# Dual_Horizontal_Breakout_Module.net
KiCad netlist of a schematic drawn in EAGLE
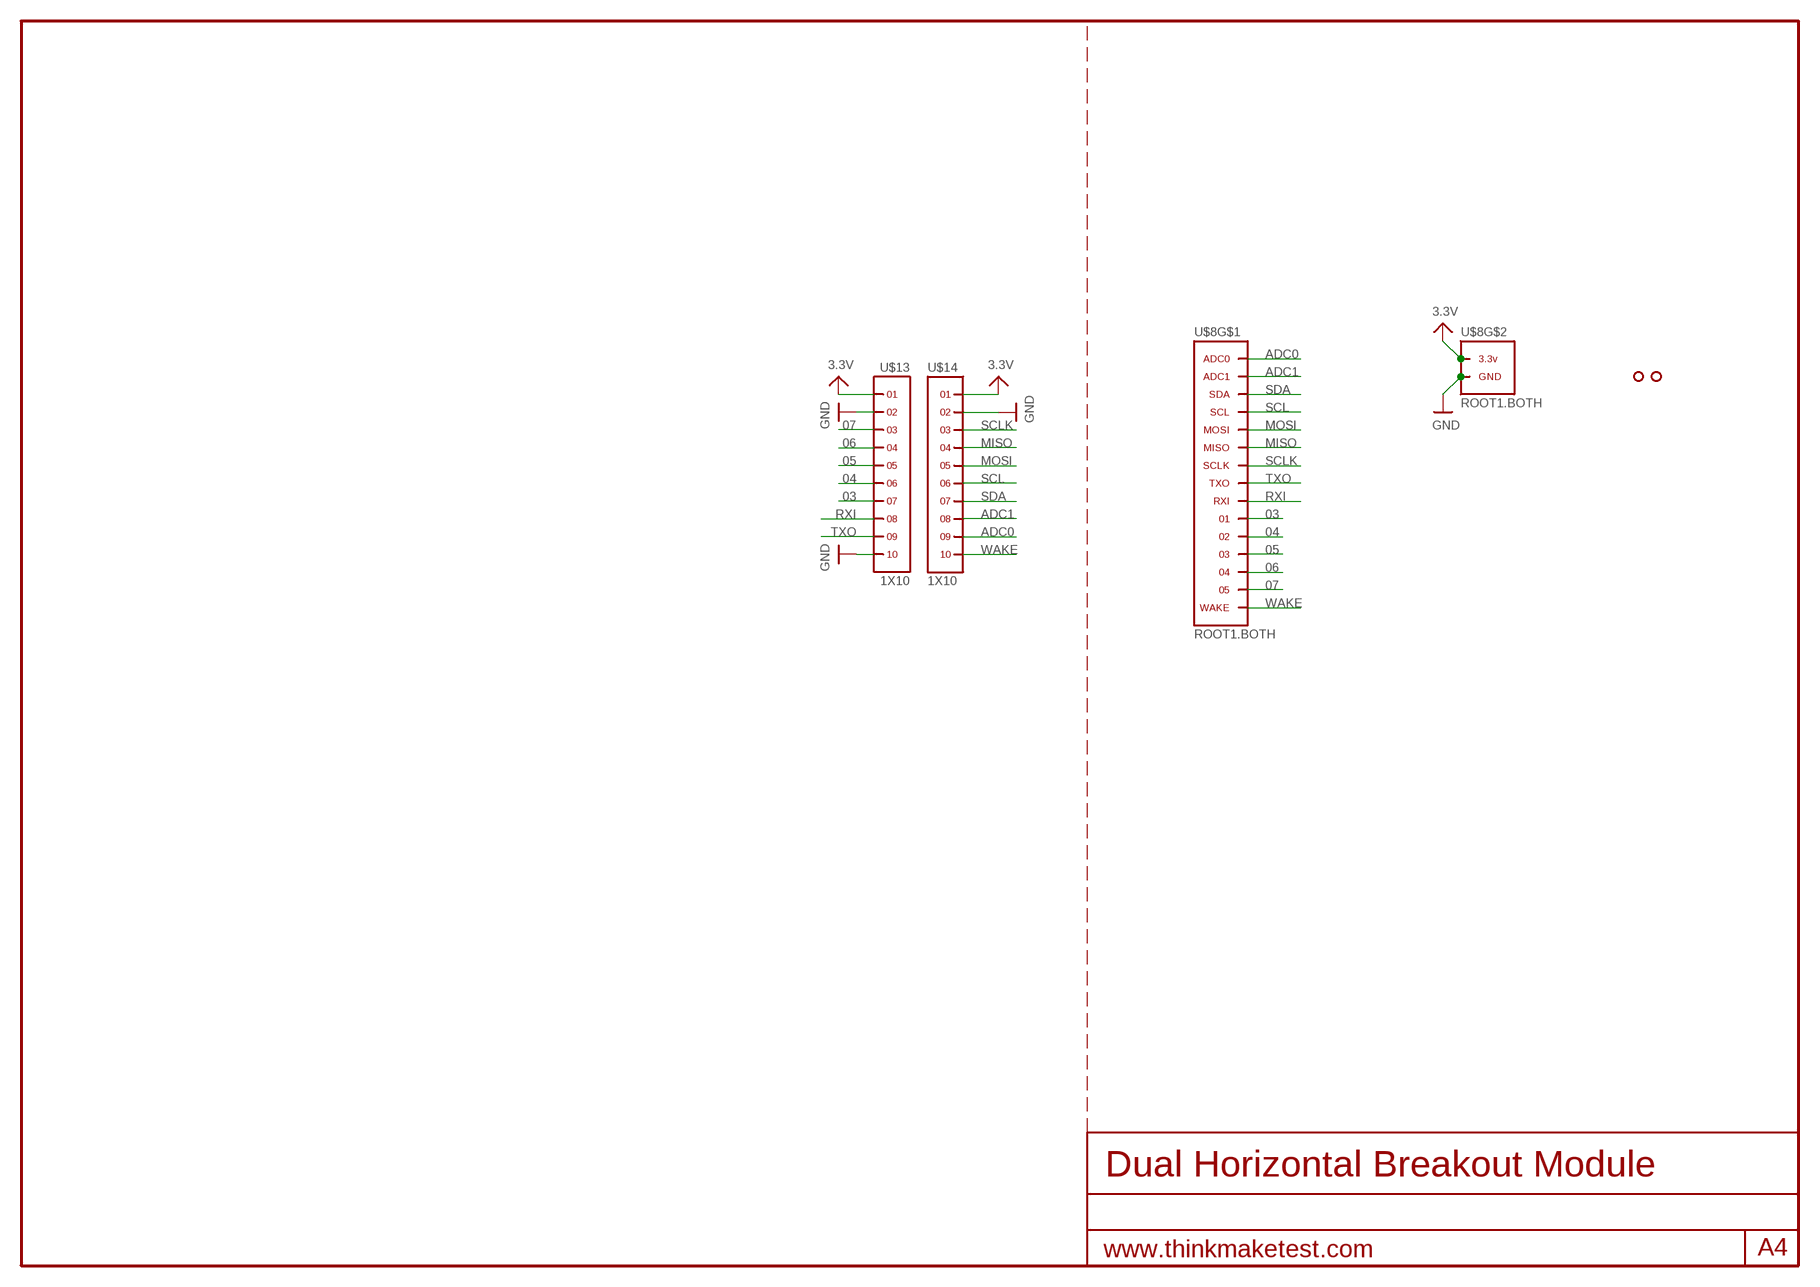
[diagram p0: schematic, sheet 1]

(export (version "E")
  (design (tool "Eeschema 10.0.6"))
  (components
    (comp (ref "U$3")
      (value "HOLE.2MM")
      (footprint "eagle-import:2MM")
      (libsource (lib "eagle-import") (part "HOLE.2MM"))
    )
    (comp (ref "U$4")
      (value "HOLE.2MM")
      (footprint "eagle-import:2MM")
      (libsource (lib "eagle-import") (part "HOLE.2MM"))
    )
    (comp (ref "U$8")
      (value "ROOT1.BOTH")
      (footprint "eagle-import:ROOT1.BOTH")
      (libsource (lib "eagle-import") (part "ROOT1.BOTH"))
    )
    (comp (ref "U$13")
      (value "1X10")
      (footprint "eagle-import:1X10")
      (libsource (lib "eagle-import") (part "1X10"))
    )
    (comp (ref "U$14")
      (value "1X10")
      (footprint "eagle-import:1X10")
      (libsource (lib "eagle-import") (part "1X10"))
    )
  )
  (nets
    (net (code "1") (name "/03") (class "Default")
      (node (ref "U$13") (pin "7") (pinfunction "7_7") (pintype "bidirectional"))
      (node (ref "U$8") (pin "03") (pinfunction "01_03") (pintype "bidirectional"))
      (node (ref "U$8") (pin "03@1") (pinfunction "01_03@1") (pintype "bidirectional"))
      (node (ref "U$8") (pin "03@VIA") (pinfunction "01_03@VIA") (pintype "bidirectional"))
    )
    (net (code "2") (name "/04") (class "Default")
      (node (ref "U$13") (pin "6") (pinfunction "6_6") (pintype "bidirectional"))
      (node (ref "U$8") (pin "04") (pinfunction "02_04") (pintype "bidirectional"))
      (node (ref "U$8") (pin "04@1") (pinfunction "02_04@1") (pintype "bidirectional"))
      (node (ref "U$8") (pin "04@VIA") (pinfunction "02_04@VIA") (pintype "bidirectional"))
    )
    (net (code "3") (name "/05") (class "Default")
      (node (ref "U$13") (pin "5") (pinfunction "5_5") (pintype "bidirectional"))
      (node (ref "U$8") (pin "05") (pinfunction "03_05") (pintype "bidirectional"))
      (node (ref "U$8") (pin "05@1") (pinfunction "03_05@1") (pintype "bidirectional"))
      (node (ref "U$8") (pin "05@VIA") (pinfunction "03_05@VIA") (pintype "bidirectional"))
    )
    (net (code "4") (name "/06") (class "Default")
      (node (ref "U$13") (pin "4") (pinfunction "4_4") (pintype "bidirectional"))
      (node (ref "U$8") (pin "06") (pinfunction "04_06") (pintype "bidirectional"))
      (node (ref "U$8") (pin "06@1") (pinfunction "04_06@1") (pintype "bidirectional"))
      (node (ref "U$8") (pin "06@VIA") (pinfunction "04_06@VIA") (pintype "bidirectional"))
    )
    (net (code "5") (name "/07") (class "Default")
      (node (ref "U$13") (pin "3") (pinfunction "3_3") (pintype "bidirectional"))
      (node (ref "U$8") (pin "07") (pinfunction "05_07") (pintype "bidirectional"))
      (node (ref "U$8") (pin "07@1") (pinfunction "05_07@1") (pintype "bidirectional"))
      (node (ref "U$8") (pin "07@VIA") (pinfunction "05_07@VIA") (pintype "bidirectional"))
    )
    (net (code "6") (name "/ADC0") (class "Default")
      (node (ref "U$14") (pin "9") (pinfunction "9_9") (pintype "bidirectional"))
      (node (ref "U$8") (pin "ADC0") (pinfunction "ADC0_ADC0") (pintype "bidirectional"))
      (node (ref "U$8") (pin "ADC0@1") (pinfunction "ADC0_ADC0@1") (pintype "bidirectional"))
      (node (ref "U$8") (pin "ADC0@VIA") (pinfunction "ADC0_ADC0@VIA") (pintype "bidirectional"))
    )
    (net (code "7") (name "/ADC1") (class "Default")
      (node (ref "U$14") (pin "8") (pinfunction "8_8") (pintype "bidirectional"))
      (node (ref "U$8") (pin "ADC1") (pinfunction "ADC1_ADC1") (pintype "bidirectional"))
      (node (ref "U$8") (pin "ADC1@1") (pinfunction "ADC1_ADC1@1") (pintype "bidirectional"))
      (node (ref "U$8") (pin "ADC1@VIA") (pinfunction "ADC1_ADC1@VIA") (pintype "bidirectional"))
    )
    (net (code "8") (name "/MISO") (class "Default")
      (node (ref "U$14") (pin "4") (pinfunction "4_4") (pintype "bidirectional"))
      (node (ref "U$8") (pin "MISO") (pinfunction "MISO_MISO") (pintype "bidirectional"))
      (node (ref "U$8") (pin "MISO@1") (pinfunction "MISO_MISO@1") (pintype "bidirectional"))
      (node (ref "U$8") (pin "MISO@VIA") (pinfunction "MISO_MISO@VIA") (pintype "bidirectional"))
    )
    (net (code "9") (name "/MOSI") (class "Default")
      (node (ref "U$14") (pin "5") (pinfunction "5_5") (pintype "bidirectional"))
      (node (ref "U$8") (pin "MOSI") (pinfunction "MOSI_MOSI") (pintype "bidirectional"))
      (node (ref "U$8") (pin "MOSI@1") (pinfunction "MOSI_MOSI@1") (pintype "bidirectional"))
      (node (ref "U$8") (pin "MOSI@VIA") (pinfunction "MOSI_MOSI@VIA") (pintype "bidirectional"))
    )
    (net (code "10") (name "/RXI") (class "Default")
      (node (ref "U$13") (pin "8") (pinfunction "8_8") (pintype "bidirectional"))
      (node (ref "U$8") (pin "02") (pinfunction "RXI_02") (pintype "bidirectional"))
      (node (ref "U$8") (pin "02@1") (pinfunction "RXI_02@1") (pintype "bidirectional"))
      (node (ref "U$8") (pin "02@VIA") (pinfunction "RXI_02@VIA") (pintype "bidirectional"))
    )
    (net (code "11") (name "/SCL") (class "Default")
      (node (ref "U$14") (pin "6") (pinfunction "6_6") (pintype "bidirectional"))
      (node (ref "U$8") (pin "SCL") (pinfunction "SCL_SCL") (pintype "bidirectional"))
      (node (ref "U$8") (pin "SCL@1") (pinfunction "SCL_SCL@1") (pintype "bidirectional"))
      (node (ref "U$8") (pin "SCL@VIA") (pinfunction "SCL_SCL@VIA") (pintype "bidirectional"))
    )
    (net (code "12") (name "/SCLK") (class "Default")
      (node (ref "U$14") (pin "3") (pinfunction "3_3") (pintype "bidirectional"))
      (node (ref "U$8") (pin "SCLK") (pinfunction "SCLK_SCLK") (pintype "bidirectional"))
      (node (ref "U$8") (pin "SCLK@1") (pinfunction "SCLK_SCLK@1") (pintype "bidirectional"))
      (node (ref "U$8") (pin "SCLK@VIA") (pinfunction "SCLK_SCLK@VIA") (pintype "bidirectional"))
    )
    (net (code "13") (name "/SDA") (class "Default")
      (node (ref "U$14") (pin "7") (pinfunction "7_7") (pintype "bidirectional"))
      (node (ref "U$8") (pin "SDA") (pinfunction "SDA_SDA") (pintype "bidirectional"))
      (node (ref "U$8") (pin "SDA@1") (pinfunction "SDA_SDA@1") (pintype "bidirectional"))
      (node (ref "U$8") (pin "SDA@VIA") (pinfunction "SDA_SDA@VIA") (pintype "bidirectional"))
    )
    (net (code "14") (name "/TXO") (class "Default")
      (node (ref "U$13") (pin "9") (pinfunction "9_9") (pintype "bidirectional"))
      (node (ref "U$8") (pin "01") (pinfunction "TXO_01") (pintype "bidirectional"))
      (node (ref "U$8") (pin "01@1") (pinfunction "TXO_01@1") (pintype "bidirectional"))
      (node (ref "U$8") (pin "01@VIA") (pinfunction "TXO_01@VIA") (pintype "bidirectional"))
    )
    (net (code "15") (name "/WAKE") (class "Default")
      (node (ref "U$14") (pin "10") (pinfunction "10_10") (pintype "bidirectional"))
      (node (ref "U$8") (pin "WAKE") (pinfunction "WAKE_WAKE") (pintype "bidirectional"))
      (node (ref "U$8") (pin "WAKE@1") (pinfunction "WAKE_WAKE@1") (pintype "bidirectional"))
      (node (ref "U$8") (pin "WAKE@VIA") (pinfunction "WAKE_WAKE@VIA") (pintype "bidirectional"))
    )
    (net (code "16") (name "3.3V") (class "Default")
      (node (ref "U$13") (pin "1") (pinfunction "1_1") (pintype "bidirectional"))
      (node (ref "U$14") (pin "1") (pinfunction "1_1") (pintype "bidirectional"))
      (node (ref "U$8") (pin "3.3V@1") (pinfunction "3.3V_3.3V@1") (pintype "bidirectional"))
      (node (ref "U$8") (pin "3.3V@10") (pinfunction "3.3V_3.3V@10") (pintype "bidirectional"))
      (node (ref "U$8") (pin "3.3V@2") (pinfunction "3.3V_3.3V@2") (pintype "bidirectional"))
      (node (ref "U$8") (pin "3.3V@3") (pinfunction "3.3V_3.3V@3") (pintype "bidirectional"))
      (node (ref "U$8") (pin "3.3V@4") (pinfunction "3.3V_3.3V@4") (pintype "bidirectional"))
      (node (ref "U$8") (pin "3.3V@5") (pinfunction "3.3V_3.3V@5") (pintype "bidirectional"))
      (node (ref "U$8") (pin "3.3V@6") (pinfunction "3.3V_3.3V@6") (pintype "bidirectional"))
      (node (ref "U$8") (pin "3.3V@7") (pinfunction "3.3V_3.3V@7") (pintype "bidirectional"))
      (node (ref "U$8") (pin "3.3V@8") (pinfunction "3.3V_3.3V@8") (pintype "bidirectional"))
      (node (ref "U$8") (pin "3.3V@9") (pinfunction "3.3V_3.3V@9") (pintype "bidirectional"))
      (node (ref "U$8") (pin "3.3V@VIA") (pinfunction "3.3V_3.3V@VIA") (pintype "bidirectional"))
    )
    (net (code "17") (name "GND") (class "Default")
      (node (ref "U$13") (pin "10") (pinfunction "10_10") (pintype "bidirectional"))
      (node (ref "U$13") (pin "2") (pinfunction "2_2") (pintype "bidirectional"))
      (node (ref "U$14") (pin "2") (pinfunction "2_2") (pintype "bidirectional"))
      (node (ref "U$8") (pin "GND@1") (pinfunction "GND_GND@1") (pintype "bidirectional"))
      (node (ref "U$8") (pin "GND@10") (pinfunction "GND_GND@10") (pintype "bidirectional"))
      (node (ref "U$8") (pin "GND@11") (pinfunction "GND_GND@11") (pintype "bidirectional"))
      (node (ref "U$8") (pin "GND@12") (pinfunction "GND_GND@12") (pintype "bidirectional"))
      (node (ref "U$8") (pin "GND@13") (pinfunction "GND_GND@13") (pintype "bidirectional"))
      (node (ref "U$8") (pin "GND@14") (pinfunction "GND_GND@14") (pintype "bidirectional"))
      (node (ref "U$8") (pin "GND@15") (pinfunction "GND_GND@15") (pintype "bidirectional"))
      (node (ref "U$8") (pin "GND@16") (pinfunction "GND_GND@16") (pintype "bidirectional"))
      (node (ref "U$8") (pin "GND@17") (pinfunction "GND_GND@17") (pintype "bidirectional"))
      (node (ref "U$8") (pin "GND@18") (pinfunction "GND_GND@18") (pintype "bidirectional"))
      (node (ref "U$8") (pin "GND@19") (pinfunction "GND_GND@19") (pintype "bidirectional"))
      (node (ref "U$8") (pin "GND@2") (pinfunction "GND_GND@2") (pintype "bidirectional"))
      (node (ref "U$8") (pin "GND@20") (pinfunction "GND_GND@20") (pintype "bidirectional"))
      (node (ref "U$8") (pin "GND@3") (pinfunction "GND_GND@3") (pintype "bidirectional"))
      (node (ref "U$8") (pin "GND@4") (pinfunction "GND_GND@4") (pintype "bidirectional"))
      (node (ref "U$8") (pin "GND@5") (pinfunction "GND_GND@5") (pintype "bidirectional"))
      (node (ref "U$8") (pin "GND@6") (pinfunction "GND_GND@6") (pintype "bidirectional"))
      (node (ref "U$8") (pin "GND@7") (pinfunction "GND_GND@7") (pintype "bidirectional"))
      (node (ref "U$8") (pin "GND@8") (pinfunction "GND_GND@8") (pintype "bidirectional"))
      (node (ref "U$8") (pin "GND@9") (pinfunction "GND_GND@9") (pintype "bidirectional"))
      (node (ref "U$8") (pin "GND@VIA") (pinfunction "GND_GND@VIA") (pintype "bidirectional"))
    )
  )
)
